# IronKid_ISTA.net
KiCad netlist of a schematic drawn in EAGLE
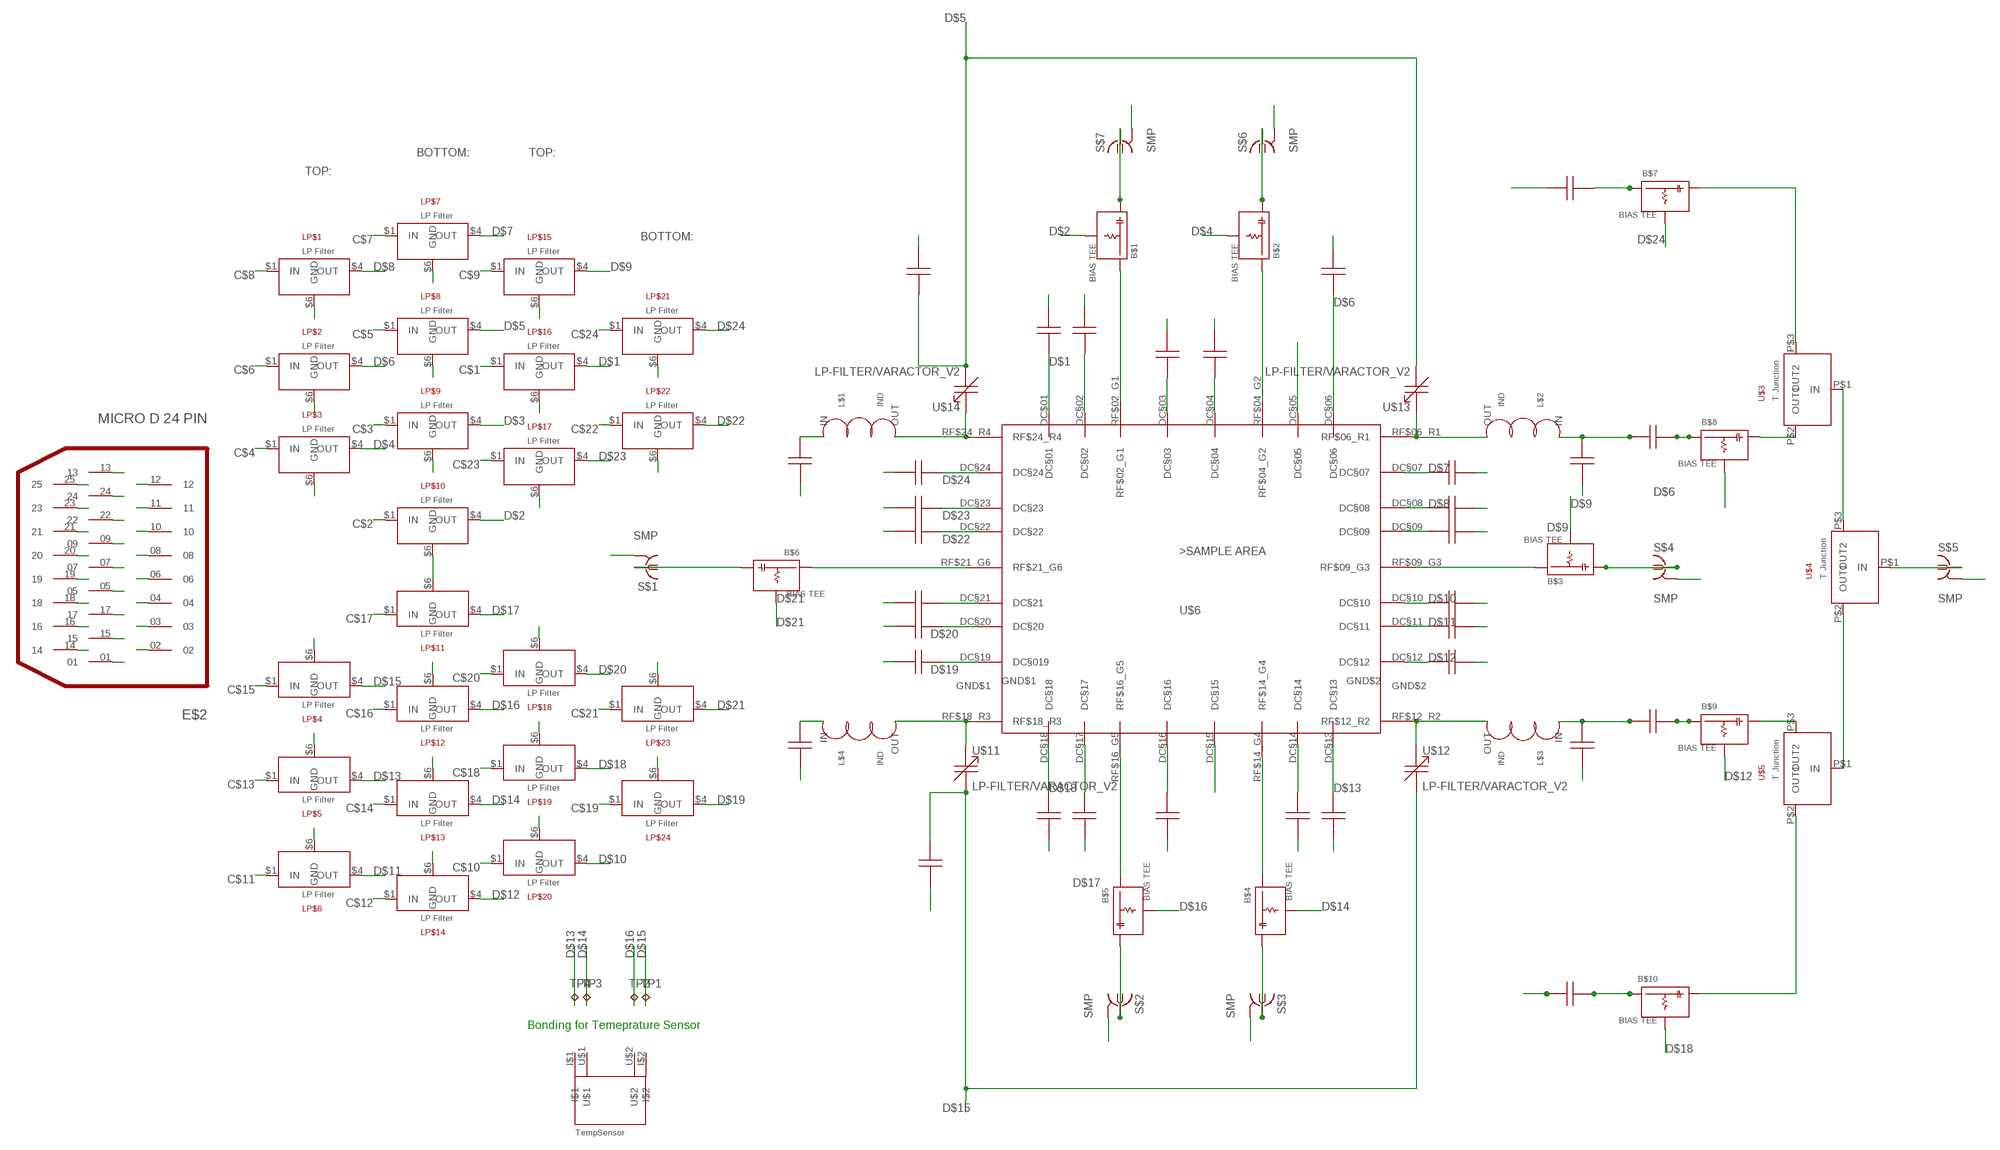
[diagram p0: schematic, sheet 1, part 1 of 2]
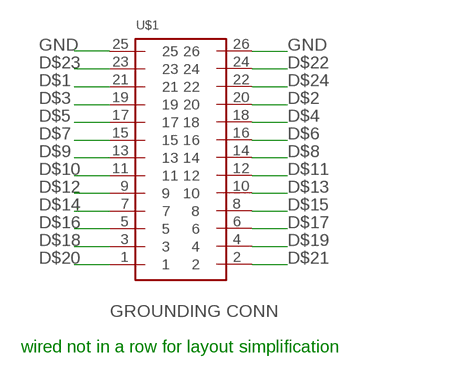
[diagram p1: schematic, sheet 1, part 2 of 2]

(export (version "E")
  (design (tool "Eeschema 10.0.6"))
  (components
    (comp (ref "B$1")
      (value "BIASTEEDOWN2")
      (footprint "eagle-import:BIAS_TEE_DOWN_0603_V02")
      (libsource (lib "eagle-import") (part "BIASTEEDOWN2"))
    )
    (comp (ref "B$2")
      (value "BIASTEEUP1")
      (footprint "eagle-import:BIAS_TEE_UP_0603")
      (libsource (lib "eagle-import") (part "BIASTEEUP1"))
    )
    (comp (ref "B$3")
      (value "BIASTEEDOWN1")
      (footprint "eagle-import:BIAS_TEE_DOWN_0603")
      (libsource (lib "eagle-import") (part "BIASTEEDOWN1"))
    )
    (comp (ref "B$4")
      (value "BIASTEEDOWN1")
      (footprint "eagle-import:BIAS_TEE_DOWN_0603")
      (libsource (lib "eagle-import") (part "BIASTEEDOWN1"))
    )
    (comp (ref "B$5")
      (value "BIASTEEUP2")
      (footprint "eagle-import:BIAS_TEE_UP_0603_V02")
      (libsource (lib "eagle-import") (part "BIASTEEUP2"))
    )
    (comp (ref "B$6")
      (value "BIASTEEDOWN1")
      (footprint "eagle-import:BIAS_TEE_DOWN_0603")
      (libsource (lib "eagle-import") (part "BIASTEEDOWN1"))
    )
    (comp (ref "B$7")
      (value "BIASTEEUP1")
      (footprint "eagle-import:BIAS_TEE_UP_0603")
      (libsource (lib "eagle-import") (part "BIASTEEUP1"))
    )
    (comp (ref "B$8")
      (value "BIASTEEDOWN1")
      (footprint "eagle-import:BIAS_TEE_DOWN_0603")
      (libsource (lib "eagle-import") (part "BIASTEEDOWN1"))
    )
    (comp (ref "B$9")
      (value "BIASTEEUP1")
      (footprint "eagle-import:BIAS_TEE_UP_0603")
      (libsource (lib "eagle-import") (part "BIASTEEUP1"))
    )
    (comp (ref "B$10")
      (value "BIASTEEDOWN1")
      (footprint "eagle-import:BIAS_TEE_DOWN_0603")
      (libsource (lib "eagle-import") (part "BIASTEEDOWN1"))
    )
    (comp (ref "E$2")
      (value "25_SOCKET_M83513(13-DPINOUT2")
      (footprint "eagle-import:25_SOCKET_M83513_13-D_V2")
      (libsource (lib "eagle-import") (part "25_SOCKET_M83513(13-DPINOUT2"))
    )
    (comp (ref "L$1")
      (value "L_MATCH")
      (footprint "eagle-import:L_MATCH")
      (libsource (lib "eagle-import") (part "L_MATCH"))
    )
    (comp (ref "L$2")
      (value "L_MATCH")
      (footprint "eagle-import:L_MATCH")
      (libsource (lib "eagle-import") (part "L_MATCH"))
    )
    (comp (ref "L$3")
      (value "L_MATCH")
      (footprint "eagle-import:L_MATCH")
      (libsource (lib "eagle-import") (part "L_MATCH"))
    )
    (comp (ref "L$4")
      (value "L_MATCH")
      (footprint "eagle-import:L_MATCH")
      (libsource (lib "eagle-import") (part "L_MATCH"))
    )
    (comp (ref "LP$1")
      (value "LP-FILTER/1-STAGETOP")
      (footprint "eagle-import:LP-FILTER_1_STAGE_OS_0603_TOP")
      (libsource (lib "eagle-import") (part "LP-FILTER/1-STAGETOP"))
    )
    (comp (ref "LP$2")
      (value "LP-FILTER/1-STAGETOP")
      (footprint "eagle-import:LP-FILTER_1_STAGE_OS_0603_TOP")
      (libsource (lib "eagle-import") (part "LP-FILTER/1-STAGETOP"))
    )
    (comp (ref "LP$3")
      (value "LP-FILTER/1-STAGETOP")
      (footprint "eagle-import:LP-FILTER_1_STAGE_OS_0603_TOP")
      (libsource (lib "eagle-import") (part "LP-FILTER/1-STAGETOP"))
    )
    (comp (ref "LP$4")
      (value "LP-FILTER/1-STAGETOP")
      (footprint "eagle-import:LP-FILTER_1_STAGE_OS_0603_TOP")
      (libsource (lib "eagle-import") (part "LP-FILTER/1-STAGETOP"))
    )
    (comp (ref "LP$5")
      (value "LP-FILTER/1-STAGETOP")
      (footprint "eagle-import:LP-FILTER_1_STAGE_OS_0603_TOP")
      (libsource (lib "eagle-import") (part "LP-FILTER/1-STAGETOP"))
    )
    (comp (ref "LP$6")
      (value "LP-FILTER/1-STAGETOP")
      (footprint "eagle-import:LP-FILTER_1_STAGE_OS_0603_TOP")
      (libsource (lib "eagle-import") (part "LP-FILTER/1-STAGETOP"))
    )
    (comp (ref "LP$7")
      (value "LP-FILTER/1-STAGEBOT")
      (footprint "eagle-import:LP-FILTER_1_STAGE_OS_0603_BOTTOM")
      (libsource (lib "eagle-import") (part "LP-FILTER/1-STAGEBOT"))
    )
    (comp (ref "LP$8")
      (value "LP-FILTER/1-STAGEBOT")
      (footprint "eagle-import:LP-FILTER_1_STAGE_OS_0603_BOTTOM")
      (libsource (lib "eagle-import") (part "LP-FILTER/1-STAGEBOT"))
    )
    (comp (ref "LP$9")
      (value "LP-FILTER/1-STAGEBOT")
      (footprint "eagle-import:LP-FILTER_1_STAGE_OS_0603_BOTTOM")
      (libsource (lib "eagle-import") (part "LP-FILTER/1-STAGEBOT"))
    )
    (comp (ref "LP$10")
      (value "LP-FILTER/1-STAGEBOT")
      (footprint "eagle-import:LP-FILTER_1_STAGE_OS_0603_BOTTOM")
      (libsource (lib "eagle-import") (part "LP-FILTER/1-STAGEBOT"))
    )
    (comp (ref "LP$11")
      (value "LP-FILTER/1-STAGEBOT")
      (footprint "eagle-import:LP-FILTER_1_STAGE_OS_0603_BOTTOM")
      (libsource (lib "eagle-import") (part "LP-FILTER/1-STAGEBOT"))
    )
    (comp (ref "LP$12")
      (value "LP-FILTER/1-STAGEBOT")
      (footprint "eagle-import:LP-FILTER_1_STAGE_OS_0603_BOTTOM")
      (libsource (lib "eagle-import") (part "LP-FILTER/1-STAGEBOT"))
    )
    (comp (ref "LP$13")
      (value "LP-FILTER/1-STAGEBOT")
      (footprint "eagle-import:LP-FILTER_1_STAGE_OS_0603_BOTTOM")
      (libsource (lib "eagle-import") (part "LP-FILTER/1-STAGEBOT"))
    )
    (comp (ref "LP$14")
      (value "LP-FILTER/1-STAGEBOT")
      (footprint "eagle-import:LP-FILTER_1_STAGE_OS_0603_BOTTOM")
      (libsource (lib "eagle-import") (part "LP-FILTER/1-STAGEBOT"))
    )
    (comp (ref "LP$15")
      (value "LP-FILTER/1-STAGETOP")
      (footprint "eagle-import:LP-FILTER_1_STAGE_OS_0603_TOP")
      (libsource (lib "eagle-import") (part "LP-FILTER/1-STAGETOP"))
    )
    (comp (ref "LP$16")
      (value "LP-FILTER/1-STAGETOP")
      (footprint "eagle-import:LP-FILTER_1_STAGE_OS_0603_TOP")
      (libsource (lib "eagle-import") (part "LP-FILTER/1-STAGETOP"))
    )
    (comp (ref "LP$17")
      (value "LP-FILTER/1-STAGETOP")
      (footprint "eagle-import:LP-FILTER_1_STAGE_OS_0603_TOP")
      (libsource (lib "eagle-import") (part "LP-FILTER/1-STAGETOP"))
    )
    (comp (ref "LP$18")
      (value "LP-FILTER/1-STAGETOP")
      (footprint "eagle-import:LP-FILTER_1_STAGE_OS_0603_TOP")
      (libsource (lib "eagle-import") (part "LP-FILTER/1-STAGETOP"))
    )
    (comp (ref "LP$19")
      (value "LP-FILTER/1-STAGETOP")
      (footprint "eagle-import:LP-FILTER_1_STAGE_OS_0603_TOP")
      (libsource (lib "eagle-import") (part "LP-FILTER/1-STAGETOP"))
    )
    (comp (ref "LP$20")
      (value "LP-FILTER/1-STAGETOP")
      (footprint "eagle-import:LP-FILTER_1_STAGE_OS_0603_TOP")
      (libsource (lib "eagle-import") (part "LP-FILTER/1-STAGETOP"))
    )
    (comp (ref "LP$21")
      (value "LP-FILTER/1-STAGEBOT")
      (footprint "eagle-import:LP-FILTER_1_STAGE_OS_0603_BOTTOM")
      (libsource (lib "eagle-import") (part "LP-FILTER/1-STAGEBOT"))
    )
    (comp (ref "LP$22")
      (value "LP-FILTER/1-STAGEBOT")
      (footprint "eagle-import:LP-FILTER_1_STAGE_OS_0603_BOTTOM")
      (libsource (lib "eagle-import") (part "LP-FILTER/1-STAGEBOT"))
    )
    (comp (ref "LP$23")
      (value "LP-FILTER/1-STAGEBOT")
      (footprint "eagle-import:LP-FILTER_1_STAGE_OS_0603_BOTTOM")
      (libsource (lib "eagle-import") (part "LP-FILTER/1-STAGEBOT"))
    )
    (comp (ref "LP$24")
      (value "LP-FILTER/1-STAGEBOT")
      (footprint "eagle-import:LP-FILTER_1_STAGE_OS_0603_BOTTOM")
      (libsource (lib "eagle-import") (part "LP-FILTER/1-STAGEBOT"))
    )
    (comp (ref "S$1")
      (value "MC-921WIDE")
      (footprint "eagle-import:SMP_STRAIGHT_MINI_WIDE")
      (libsource (lib "eagle-import") (part "MC-921WIDE"))
    )
    (comp (ref "S$2")
      (value "MC-921WIDE")
      (footprint "eagle-import:SMP_STRAIGHT_MINI_WIDE")
      (libsource (lib "eagle-import") (part "MC-921WIDE"))
    )
    (comp (ref "S$3")
      (value "MC-921WIDE")
      (footprint "eagle-import:SMP_STRAIGHT_MINI_WIDE")
      (libsource (lib "eagle-import") (part "MC-921WIDE"))
    )
    (comp (ref "S$4")
      (value "MC-921WIDE")
      (footprint "eagle-import:SMP_STRAIGHT_MINI_WIDE")
      (libsource (lib "eagle-import") (part "MC-921WIDE"))
    )
    (comp (ref "S$5")
      (value "MC-921WIDE")
      (footprint "eagle-import:SMP_STRAIGHT_MINI_WIDE")
      (libsource (lib "eagle-import") (part "MC-921WIDE"))
    )
    (comp (ref "S$6")
      (value "MC-921WIDE")
      (footprint "eagle-import:SMP_STRAIGHT_MINI_WIDE")
      (libsource (lib "eagle-import") (part "MC-921WIDE"))
    )
    (comp (ref "S$7")
      (value "MC-921WIDE")
      (footprint "eagle-import:SMP_STRAIGHT_MINI_WIDE")
      (libsource (lib "eagle-import") (part "MC-921WIDE"))
    )
    (comp (ref "TP1")
      (value "TPTP07SQ")
      (footprint "eagle-import:TP07SQ")
      (libsource (lib "eagle-import") (part "TPTP07SQ"))
    )
    (comp (ref "TP2")
      (value "TPTP07SQ")
      (footprint "eagle-import:TP07SQ")
      (libsource (lib "eagle-import") (part "TPTP07SQ"))
    )
    (comp (ref "TP3")
      (value "TPTP07SQ")
      (footprint "eagle-import:TP07SQ")
      (libsource (lib "eagle-import") (part "TPTP07SQ"))
    )
    (comp (ref "TP4")
      (value "TPTP07SQ")
      (footprint "eagle-import:TP07SQ")
      (libsource (lib "eagle-import") (part "TPTP07SQ"))
    )
    (comp (ref "U$1")
      (value "MEC8-113-02-L-D-RA1MBRD")
      (footprint "eagle-import:MEC8-113-02-L-D-RA1")
      (libsource (lib "eagle-import") (part "MEC8-113-02-L-D-RA1MBRD"))
    )
    (comp (ref "U$2")
      (value "TEMPSENS")
      (footprint "eagle-import:RX-BR_V1")
      (libsource (lib "eagle-import") (part "TEMPSENS"))
    )
    (comp (ref "U$3")
      (value "TJUNCTION")
      (footprint "eagle-import:T_JUNCTION_0.3MM")
      (libsource (lib "eagle-import") (part "TJUNCTION"))
    )
    (comp (ref "U$4")
      (value "TJUNCTION")
      (footprint "eagle-import:T_JUNCTION_0.3MM")
      (libsource (lib "eagle-import") (part "TJUNCTION"))
    )
    (comp (ref "U$5")
      (value "TJUNCTION")
      (footprint "eagle-import:T_JUNCTION_0.3MM")
      (libsource (lib "eagle-import") (part "TJUNCTION"))
    )
    (comp (ref "U$6")
      (value "24DC+10RF_V3.0")
      (footprint "eagle-import:24DC+10RF_400MU-PADS_0.7X0.7_V3.0")
      (libsource (lib "eagle-import") (part "24DC+10RF_V3.0"))
    )
    (comp (ref "U$7")
      (value "LP-FILTER/CAPACITOR/0603THIN")
      (footprint "eagle-import:LP-FILTER_CAPACITOR_0603_BOTTOM")
      (libsource (lib "eagle-import") (part "LP-FILTER/CAPACITOR/0603THIN"))
    )
    (comp (ref "U$8")
      (value "LP-FILTER/CAPACITOR/0603THIN")
      (footprint "eagle-import:LP-FILTER_CAPACITOR_0603_BOTTOM")
      (libsource (lib "eagle-import") (part "LP-FILTER/CAPACITOR/0603THIN"))
    )
    (comp (ref "U$9")
      (value "LP-FILTER/CAPACITOR/0603THIN")
      (footprint "eagle-import:LP-FILTER_CAPACITOR_0603_BOTTOM")
      (libsource (lib "eagle-import") (part "LP-FILTER/CAPACITOR/0603THIN"))
    )
    (comp (ref "U$10")
      (value "LP-FILTER/CAPACITOR/0603THIN")
      (footprint "eagle-import:LP-FILTER_CAPACITOR_0603_BOTTOM")
      (libsource (lib "eagle-import") (part "LP-FILTER/CAPACITOR/0603THIN"))
    )
    (comp (ref "U$11")
      (value "LP-FILTER/VARACTOR_V2")
      (footprint "eagle-import:LP-FILTER_VARACTOR_V2")
      (libsource (lib "eagle-import") (part "LP-FILTER/VARACTOR_V2"))
    )
    (comp (ref "U$12")
      (value "LP-FILTER/VARACTOR_V2")
      (footprint "eagle-import:LP-FILTER_VARACTOR_V2")
      (libsource (lib "eagle-import") (part "LP-FILTER/VARACTOR_V2"))
    )
    (comp (ref "U$13")
      (value "LP-FILTER/VARACTOR_V2")
      (footprint "eagle-import:LP-FILTER_VARACTOR_V2")
      (libsource (lib "eagle-import") (part "LP-FILTER/VARACTOR_V2"))
    )
    (comp (ref "U$14")
      (value "LP-FILTER/VARACTOR_V2")
      (footprint "eagle-import:LP-FILTER_VARACTOR_V2")
      (libsource (lib "eagle-import") (part "LP-FILTER/VARACTOR_V2"))
    )
    (comp (ref "U$15")
      (value "LP-FILTER/CAPACITOR/0603NORMAL")
      (footprint "eagle-import:LP-FILTER_CAPACITOR_0603_BOTTOM_V2")
      (libsource (lib "eagle-import") (part "LP-FILTER/CAPACITOR/0603NORMAL"))
    )
    (comp (ref "U$16")
      (value "LP-FILTER/CAPACITOR/0603NORMAL")
      (footprint "eagle-import:LP-FILTER_CAPACITOR_0603_BOTTOM_V2")
      (libsource (lib "eagle-import") (part "LP-FILTER/CAPACITOR/0603NORMAL"))
    )
    (comp (ref "U$17")
      (value "LP-FILTER/CAPACITOR/0603THIN")
      (footprint "eagle-import:LP-FILTER_CAPACITOR_0603_BOTTOM")
      (libsource (lib "eagle-import") (part "LP-FILTER/CAPACITOR/0603THIN"))
    )
    (comp (ref "U$18")
      (value "LP-FILTER/CAPACITOR/0603THIN")
      (footprint "eagle-import:LP-FILTER_CAPACITOR_0603_BOTTOM")
      (libsource (lib "eagle-import") (part "LP-FILTER/CAPACITOR/0603THIN"))
    )
    (comp (ref "U$19")
      (value "LP-FILTER/CAPACITOR/0603THIN")
      (footprint "eagle-import:LP-FILTER_CAPACITOR_0603_BOTTOM")
      (libsource (lib "eagle-import") (part "LP-FILTER/CAPACITOR/0603THIN"))
    )
    (comp (ref "U$20")
      (value "LP-FILTER/CAPACITOR/0603THIN")
      (footprint "eagle-import:LP-FILTER_CAPACITOR_0603_BOTTOM")
      (libsource (lib "eagle-import") (part "LP-FILTER/CAPACITOR/0603THIN"))
    )
    (comp (ref "U$21")
      (value "LP-FILTER/CAPACITOR/0603NORMAL")
      (footprint "eagle-import:LP-FILTER_CAPACITOR_0603_BOTTOM_V2")
      (libsource (lib "eagle-import") (part "LP-FILTER/CAPACITOR/0603NORMAL"))
    )
    (comp (ref "U$22")
      (value "LP-FILTER/CAPACITOR/0603NORMAL")
      (footprint "eagle-import:LP-FILTER_CAPACITOR_0603_BOTTOM_V2")
      (libsource (lib "eagle-import") (part "LP-FILTER/CAPACITOR/0603NORMAL"))
    )
    (comp (ref "U$23")
      (value "LP-FILTER/CAPACITOR/0603NORMAL")
      (footprint "eagle-import:LP-FILTER_CAPACITOR_0603_BOTTOM_V2")
      (libsource (lib "eagle-import") (part "LP-FILTER/CAPACITOR/0603NORMAL"))
    )
    (comp (ref "U$24")
      (value "LP-FILTER/CAPACITOR/0603NORMAL")
      (footprint "eagle-import:LP-FILTER_CAPACITOR_0603_BOTTOM_V2")
      (libsource (lib "eagle-import") (part "LP-FILTER/CAPACITOR/0603NORMAL"))
    )
    (comp (ref "U$26")
      (value "LP-FILTER/CAPACITOR/0603NORMAL")
      (footprint "eagle-import:LP-FILTER_CAPACITOR_0603_BOTTOM_V2")
      (libsource (lib "eagle-import") (part "LP-FILTER/CAPACITOR/0603NORMAL"))
    )
    (comp (ref "U$27")
      (value "LP-FILTER/CAPACITOR/0603NORMAL")
      (footprint "eagle-import:LP-FILTER_CAPACITOR_0603_BOTTOM_V2")
      (libsource (lib "eagle-import") (part "LP-FILTER/CAPACITOR/0603NORMAL"))
    )
    (comp (ref "U$28")
      (value "LP-FILTER/CAPACITOR/0603NORMAL")
      (footprint "eagle-import:LP-FILTER_CAPACITOR_0603_BOTTOM_V2")
      (libsource (lib "eagle-import") (part "LP-FILTER/CAPACITOR/0603NORMAL"))
    )
    (comp (ref "U$29")
      (value "LP-FILTER/CAPACITOR/0603NORMAL")
      (footprint "eagle-import:LP-FILTER_CAPACITOR_0603_BOTTOM_V2")
      (libsource (lib "eagle-import") (part "LP-FILTER/CAPACITOR/0603NORMAL"))
    )
    (comp (ref "U$30")
      (value "LP-FILTER/CAPACITOR/0603NORMAL")
      (footprint "eagle-import:LP-FILTER_CAPACITOR_0603_BOTTOM_V2")
      (libsource (lib "eagle-import") (part "LP-FILTER/CAPACITOR/0603NORMAL"))
    )
    (comp (ref "U$31")
      (value "LP-FILTER/CAPACITOR/0603NORMAL")
      (footprint "eagle-import:LP-FILTER_CAPACITOR_0603_BOTTOM_V2")
      (libsource (lib "eagle-import") (part "LP-FILTER/CAPACITOR/0603NORMAL"))
    )
    (comp (ref "U$32")
      (value "LP-FILTER/CAPACITOR/0603NORMAL")
      (footprint "eagle-import:LP-FILTER_CAPACITOR_0603_BOTTOM_V2")
      (libsource (lib "eagle-import") (part "LP-FILTER/CAPACITOR/0603NORMAL"))
    )
    (comp (ref "U$33")
      (value "LP-FILTER/CAPACITOR/0603NORMAL")
      (footprint "eagle-import:LP-FILTER_CAPACITOR_0603_BOTTOM_V2")
      (libsource (lib "eagle-import") (part "LP-FILTER/CAPACITOR/0603NORMAL"))
    )
    (comp (ref "U$34")
      (value "LP-FILTER/CAPACITOR/0603NORMAL")
      (footprint "eagle-import:LP-FILTER_CAPACITOR_0603_BOTTOM_V2")
      (libsource (lib "eagle-import") (part "LP-FILTER/CAPACITOR/0603NORMAL"))
    )
    (comp (ref "U$36")
      (value "LP-FILTER/CAPACITOR/0603NORMAL")
      (footprint "eagle-import:LP-FILTER_CAPACITOR_0603_BOTTOM_V2")
      (libsource (lib "eagle-import") (part "LP-FILTER/CAPACITOR/0603NORMAL"))
    )
    (comp (ref "U$37")
      (value "LP-FILTER/CAPACITOR/0603NORMAL")
      (footprint "eagle-import:LP-FILTER_CAPACITOR_0603_BOTTOM_V2")
      (libsource (lib "eagle-import") (part "LP-FILTER/CAPACITOR/0603NORMAL"))
    )
    (comp (ref "U$38")
      (value "LP-FILTER/CAPACITOR/0603NORMAL")
      (footprint "eagle-import:LP-FILTER_CAPACITOR_0603_BOTTOM_V2")
      (libsource (lib "eagle-import") (part "LP-FILTER/CAPACITOR/0603NORMAL"))
    )
    (comp (ref "U$39")
      (value "LP-FILTER/CAPACITOR/0603NORMAL")
      (footprint "eagle-import:LP-FILTER_CAPACITOR_0603_BOTTOM_V2")
      (libsource (lib "eagle-import") (part "LP-FILTER/CAPACITOR/0603NORMAL"))
    )
    (comp (ref "U$40")
      (value "LP-FILTER/CAPACITOR/0603NORMAL")
      (footprint "eagle-import:LP-FILTER_CAPACITOR_0603_BOTTOM_V2")
      (libsource (lib "eagle-import") (part "LP-FILTER/CAPACITOR/0603NORMAL"))
    )
    (comp (ref "U$41")
      (value "LP-FILTER/CAPACITOR/0603NORMAL")
      (footprint "eagle-import:LP-FILTER_CAPACITOR_0603_BOTTOM_V2")
      (libsource (lib "eagle-import") (part "LP-FILTER/CAPACITOR/0603NORMAL"))
    )
    (comp (ref "U$42")
      (value "LP-FILTER/CAPACITOR/0603NORMAL")
      (footprint "eagle-import:LP-FILTER_CAPACITOR_0603_BOTTOM_V2")
      (libsource (lib "eagle-import") (part "LP-FILTER/CAPACITOR/0603NORMAL"))
    )
    (comp (ref "U$43")
      (value "LP-FILTER/CAPACITOR/0603NORMAL")
      (footprint "eagle-import:LP-FILTER_CAPACITOR_0603_BOTTOM_V2")
      (libsource (lib "eagle-import") (part "LP-FILTER/CAPACITOR/0603NORMAL"))
    )
    (comp (ref "U$44")
      (value "LP-FILTER/CAPACITOR/0603NORMAL")
      (footprint "eagle-import:LP-FILTER_CAPACITOR_0603_BOTTOM_V2")
      (libsource (lib "eagle-import") (part "LP-FILTER/CAPACITOR/0603NORMAL"))
    )
  )
  (nets
    (net (code "1") (name "/C$1") (class "Default")
      (node (ref "E$2") (pin "01") (pinfunction "01_01") (pintype "bidirectional"))
      (node (ref "LP$16") (pin "$1") (pinfunction "IN_$1") (pintype "bidirectional"))
    )
    (net (code "2") (name "/C$2") (class "Default")
      (node (ref "E$2") (pin "02") (pinfunction "02_02") (pintype "bidirectional"))
      (node (ref "LP$10") (pin "$1") (pinfunction "IN_$1") (pintype "bidirectional"))
    )
    (net (code "3") (name "/C$3") (class "Default")
      (node (ref "E$2") (pin "03") (pinfunction "03_03") (pintype "bidirectional"))
      (node (ref "LP$9") (pin "$1") (pinfunction "IN_$1") (pintype "bidirectional"))
    )
    (net (code "4") (name "/C$4") (class "Default")
      (node (ref "E$2") (pin "04") (pinfunction "04_04") (pintype "bidirectional"))
      (node (ref "LP$3") (pin "$1") (pinfunction "IN_$1") (pintype "bidirectional"))
    )
    (net (code "5") (name "/C$5") (class "Default")
      (node (ref "E$2") (pin "05") (pinfunction "05_05") (pintype "bidirectional"))
      (node (ref "LP$8") (pin "$1") (pinfunction "IN_$1") (pintype "bidirectional"))
    )
    (net (code "6") (name "/C$6") (class "Default")
      (node (ref "E$2") (pin "06") (pinfunction "06_06") (pintype "bidirectional"))
      (node (ref "LP$2") (pin "$1") (pinfunction "IN_$1") (pintype "bidirectional"))
    )
    (net (code "7") (name "/C$7") (class "Default")
      (node (ref "E$2") (pin "07") (pinfunction "07_07") (pintype "bidirectional"))
      (node (ref "LP$7") (pin "$1") (pinfunction "IN_$1") (pintype "bidirectional"))
    )
    (net (code "8") (name "/C$8") (class "Default")
      (node (ref "E$2") (pin "08") (pinfunction "08_08") (pintype "bidirectional"))
      (node (ref "LP$1") (pin "$1") (pinfunction "IN_$1") (pintype "bidirectional"))
    )
    (net (code "9") (name "/C$9") (class "Default")
      (node (ref "E$2") (pin "09") (pinfunction "09_09") (pintype "bidirectional"))
      (node (ref "LP$15") (pin "$1") (pinfunction "IN_$1") (pintype "bidirectional"))
    )
    (net (code "10") (name "/C$10") (class "Default")
      (node (ref "E$2") (pin "10") (pinfunction "10_10") (pintype "bidirectional"))
      (node (ref "LP$20") (pin "$1") (pinfunction "IN_$1") (pintype "bidirectional"))
    )
    (net (code "11") (name "/C$11") (class "Default")
      (node (ref "E$2") (pin "11") (pinfunction "11_11") (pintype "bidirectional"))
      (node (ref "LP$6") (pin "$1") (pinfunction "IN_$1") (pintype "bidirectional"))
    )
    (net (code "12") (name "/C$12") (class "Default")
      (node (ref "E$2") (pin "12") (pinfunction "12_12") (pintype "bidirectional"))
      (node (ref "LP$14") (pin "$1") (pinfunction "IN_$1") (pintype "bidirectional"))
    )
    (net (code "13") (name "/C$13") (class "Default")
      (node (ref "E$2") (pin "13") (pinfunction "13_13") (pintype "bidirectional"))
      (node (ref "LP$5") (pin "$1") (pinfunction "IN_$1") (pintype "bidirectional"))
    )
    (net (code "14") (name "/C$14") (class "Default")
      (node (ref "E$2") (pin "14") (pinfunction "14_14") (pintype "bidirectional"))
      (node (ref "LP$13") (pin "$1") (pinfunction "IN_$1") (pintype "bidirectional"))
    )
    (net (code "15") (name "/C$15") (class "Default")
      (node (ref "E$2") (pin "15") (pinfunction "15_15") (pintype "bidirectional"))
      (node (ref "LP$4") (pin "$1") (pinfunction "IN_$1") (pintype "bidirectional"))
    )
    (net (code "16") (name "/C$16") (class "Default")
      (node (ref "E$2") (pin "16") (pinfunction "16_16") (pintype "bidirectional"))
      (node (ref "LP$12") (pin "$1") (pinfunction "IN_$1") (pintype "bidirectional"))
    )
    (net (code "17") (name "/C$17") (class "Default")
      (node (ref "E$2") (pin "17") (pinfunction "17_17") (pintype "bidirectional"))
      (node (ref "LP$11") (pin "$1") (pinfunction "IN_$1") (pintype "bidirectional"))
    )
    (net (code "18") (name "/C$18") (class "Default")
      (node (ref "E$2") (pin "18") (pinfunction "18_18") (pintype "bidirectional"))
      (node (ref "LP$19") (pin "$1") (pinfunction "IN_$1") (pintype "bidirectional"))
    )
    (net (code "19") (name "/C$19") (class "Default")
      (node (ref "E$2") (pin "19") (pinfunction "19_19") (pintype "bidirectional"))
      (node (ref "LP$24") (pin "$1") (pinfunction "IN_$1") (pintype "bidirectional"))
    )
    (net (code "20") (name "/C$20") (class "Default")
      (node (ref "E$2") (pin "20") (pinfunction "20_20") (pintype "bidirectional"))
      (node (ref "LP$18") (pin "$1") (pinfunction "IN_$1") (pintype "bidirectional"))
    )
    (net (code "21") (name "/C$21") (class "Default")
      (node (ref "E$2") (pin "21") (pinfunction "21_21") (pintype "bidirectional"))
      (node (ref "LP$23") (pin "$1") (pinfunction "IN_$1") (pintype "bidirectional"))
    )
    (net (code "22") (name "/C$22") (class "Default")
      (node (ref "E$2") (pin "22") (pinfunction "22_22") (pintype "bidirectional"))
      (node (ref "LP$22") (pin "$1") (pinfunction "IN_$1") (pintype "bidirectional"))
    )
    (net (code "23") (name "/C$23") (class "Default")
      (node (ref "E$2") (pin "23") (pinfunction "23_23") (pintype "bidirectional"))
      (node (ref "LP$17") (pin "$1") (pinfunction "IN_$1") (pintype "bidirectional"))
    )
    (net (code "24") (name "/C$24") (class "Default")
      (node (ref "E$2") (pin "24") (pinfunction "24_24") (pintype "bidirectional"))
      (node (ref "LP$21") (pin "$1") (pinfunction "IN_$1") (pintype "bidirectional"))
    )
    (net (code "25") (name "/D$1") (class "Default")
      (node (ref "LP$16") (pin "$4") (pinfunction "OUT_$4") (pintype "bidirectional"))
      (node (ref "U$1") (pin "21") (pinfunction "21_21") (pintype "bidirectional"))
      (node (ref "U$21") (pin "OUT") (pinfunction "2_OUT") (pintype "passive"))
      (node (ref "U$6") (pin "DC$01") (pinfunction "DC§01_DC$01") (pintype "bidirectional"))
    )
    (net (code "26") (name "/D$2") (class "Default")
      (node (ref "B$1") (pin "LF") (pinfunction "LF_LF") (pintype "bidirectional"))
      (node (ref "LP$10") (pin "$4") (pinfunction "OUT_$4") (pintype "bidirectional"))
      (node (ref "U$1") (pin "20") (pinfunction "20_20") (pintype "bidirectional"))
      (node (ref "U$22") (pin "OUT") (pinfunction "2_OUT") (pintype "passive"))
      (node (ref "U$6") (pin "DC§02") (pinfunction "DC§02_DC§02") (pintype "bidirectional"))
    )
    (net (code "27") (name "/D$3") (class "Default")
      (node (ref "LP$9") (pin "$4") (pinfunction "OUT_$4") (pintype "bidirectional"))
      (node (ref "U$1") (pin "19") (pinfunction "19_19") (pintype "bidirectional"))
      (node (ref "U$23") (pin "OUT") (pinfunction "2_OUT") (pintype "passive"))
      (node (ref "U$6") (pin "DC§03") (pinfunction "DC§03_DC§03") (pintype "bidirectional"))
    )
    (net (code "28") (name "/D$4") (class "Default")
      (node (ref "B$2") (pin "LF") (pinfunction "LF_LF") (pintype "bidirectional"))
      (node (ref "LP$3") (pin "$4") (pinfunction "OUT_$4") (pintype "bidirectional"))
      (node (ref "U$1") (pin "18") (pinfunction "18_18") (pintype "bidirectional"))
      (node (ref "U$24") (pin "OUT") (pinfunction "2_OUT") (pintype "passive"))
      (node (ref "U$6") (pin "DC§04") (pinfunction "DC§04_DC§04") (pintype "bidirectional"))
    )
    (net (code "29") (name "/D$5") (class "Default")
      (node (ref "LP$8") (pin "$4") (pinfunction "OUT_$4") (pintype "bidirectional"))
      (node (ref "U$1") (pin "17") (pinfunction "17_17") (pintype "bidirectional"))
      (node (ref "U$13") (pin "OUT1") (pinfunction "2_OUT1") (pintype "passive"))
      (node (ref "U$14") (pin "OUT1") (pinfunction "2_OUT1") (pintype "passive"))
      (node (ref "U$15") (pin "OUT") (pinfunction "2_OUT") (pintype "passive"))
      (node (ref "U$6") (pin "DC§05") (pinfunction "DC§05_DC§05") (pintype "bidirectional"))
    )
    (net (code "30") (name "/D$6") (class "Default")
      (node (ref "B$8") (pin "LF") (pinfunction "LF_LF") (pintype "bidirectional"))
      (node (ref "LP$2") (pin "$4") (pinfunction "OUT_$4") (pintype "bidirectional"))
      (node (ref "U$1") (pin "16") (pinfunction "16_16") (pintype "bidirectional"))
      (node (ref "U$26") (pin "OUT") (pinfunction "2_OUT") (pintype "passive"))
      (node (ref "U$6") (pin "DC§06") (pinfunction "DC§06_DC§06") (pintype "bidirectional"))
    )
    (net (code "31") (name "/D$7") (class "Default")
      (node (ref "LP$7") (pin "$4") (pinfunction "OUT_$4") (pintype "bidirectional"))
      (node (ref "U$1") (pin "15") (pinfunction "15_15") (pintype "bidirectional"))
      (node (ref "U$27") (pin "OUT") (pinfunction "2_OUT") (pintype "passive"))
      (node (ref "U$6") (pin "DC§07") (pinfunction "DC§07_DC§07") (pintype "bidirectional"))
    )
    (net (code "32") (name "/D$8") (class "Default")
      (node (ref "LP$1") (pin "$4") (pinfunction "OUT_$4") (pintype "bidirectional"))
      (node (ref "U$1") (pin "14") (pinfunction "14_14") (pintype "bidirectional"))
      (node (ref "U$28") (pin "OUT") (pinfunction "2_OUT") (pintype "passive"))
      (node (ref "U$6") (pin "DC§08") (pinfunction "DC§08_DC§08") (pintype "bidirectional"))
    )
    (net (code "33") (name "/D$9") (class "Default")
      (node (ref "B$3") (pin "LF") (pinfunction "LF_LF") (pintype "bidirectional"))
      (node (ref "LP$15") (pin "$4") (pinfunction "OUT_$4") (pintype "bidirectional"))
      (node (ref "U$1") (pin "13") (pinfunction "13_13") (pintype "bidirectional"))
      (node (ref "U$29") (pin "OUT") (pinfunction "2_OUT") (pintype "passive"))
      (node (ref "U$6") (pin "DC§09") (pinfunction "DC§09_DC§09") (pintype "bidirectional"))
    )
    (net (code "34") (name "/D$10") (class "Default")
      (node (ref "LP$20") (pin "$4") (pinfunction "OUT_$4") (pintype "bidirectional"))
      (node (ref "U$1") (pin "11") (pinfunction "11_11") (pintype "bidirectional"))
      (node (ref "U$30") (pin "OUT") (pinfunction "2_OUT") (pintype "passive"))
      (node (ref "U$6") (pin "DC§10") (pinfunction "DC§10_DC§10") (pintype "bidirectional"))
    )
    (net (code "35") (name "/D$11") (class "Default")
      (node (ref "LP$6") (pin "$4") (pinfunction "OUT_$4") (pintype "bidirectional"))
      (node (ref "U$1") (pin "12") (pinfunction "12_12") (pintype "bidirectional"))
      (node (ref "U$31") (pin "OUT") (pinfunction "2_OUT") (pintype "passive"))
      (node (ref "U$6") (pin "DC§11") (pinfunction "DC§11_DC§11") (pintype "bidirectional"))
    )
    (net (code "36") (name "/D$12") (class "Default")
      (node (ref "B$9") (pin "LF") (pinfunction "LF_LF") (pintype "bidirectional"))
      (node (ref "LP$14") (pin "$4") (pinfunction "OUT_$4") (pintype "bidirectional"))
      (node (ref "U$1") (pin "9") (pinfunction "9_9") (pintype "bidirectional"))
      (node (ref "U$32") (pin "OUT") (pinfunction "2_OUT") (pintype "passive"))
      (node (ref "U$6") (pin "DC§12") (pinfunction "DC§12_DC§12") (pintype "bidirectional"))
    )
    (net (code "37") (name "/D$13") (class "Default")
      (node (ref "LP$5") (pin "$4") (pinfunction "OUT_$4") (pintype "bidirectional"))
      (node (ref "TP4") (pin "TP") (pinfunction "TP_TP") (pintype "input"))
      (node (ref "U$1") (pin "10") (pinfunction "10_10") (pintype "bidirectional"))
      (node (ref "U$33") (pin "OUT") (pinfunction "2_OUT") (pintype "passive"))
      (node (ref "U$6") (pin "DC§13") (pinfunction "DC§13_DC§13") (pintype "bidirectional"))
    )
    (net (code "38") (name "/D$14") (class "Default")
      (node (ref "B$4") (pin "LF") (pinfunction "LF_LF") (pintype "bidirectional"))
      (node (ref "LP$13") (pin "$4") (pinfunction "OUT_$4") (pintype "bidirectional"))
      (node (ref "TP3") (pin "TP") (pinfunction "TP_TP") (pintype "input"))
      (node (ref "U$1") (pin "7") (pinfunction "7_7") (pintype "bidirectional"))
      (node (ref "U$34") (pin "OUT") (pinfunction "2_OUT") (pintype "passive"))
      (node (ref "U$6") (pin "DC§14") (pinfunction "DC§14_DC§14") (pintype "bidirectional"))
    )
    (net (code "39") (name "/D$15") (class "Default")
      (node (ref "LP$4") (pin "$4") (pinfunction "OUT_$4") (pintype "bidirectional"))
      (node (ref "TP1") (pin "TP") (pinfunction "TP_TP") (pintype "input"))
      (node (ref "U$1") (pin "8") (pinfunction "8_8") (pintype "bidirectional"))
      (node (ref "U$11") (pin "OUT1") (pinfunction "2_OUT1") (pintype "passive"))
      (node (ref "U$12") (pin "OUT1") (pinfunction "2_OUT1") (pintype "passive"))
      (node (ref "U$16") (pin "OUT") (pinfunction "2_OUT") (pintype "passive"))
      (node (ref "U$6") (pin "DC§15") (pinfunction "DC§15_DC§15") (pintype "bidirectional"))
    )
    (net (code "40") (name "/D$16") (class "Default")
      (node (ref "B$5") (pin "LF") (pinfunction "LF_LF") (pintype "bidirectional"))
      (node (ref "LP$12") (pin "$4") (pinfunction "OUT_$4") (pintype "bidirectional"))
      (node (ref "TP2") (pin "TP") (pinfunction "TP_TP") (pintype "input"))
      (node (ref "U$1") (pin "5") (pinfunction "5_5") (pintype "bidirectional"))
      (node (ref "U$36") (pin "OUT") (pinfunction "2_OUT") (pintype "passive"))
      (node (ref "U$6") (pin "DC§16") (pinfunction "DC§16_DC§16") (pintype "bidirectional"))
    )
    (net (code "41") (name "/D$17") (class "Default")
      (node (ref "LP$11") (pin "$4") (pinfunction "OUT_$4") (pintype "bidirectional"))
      (node (ref "U$1") (pin "6") (pinfunction "6_6") (pintype "bidirectional"))
      (node (ref "U$37") (pin "OUT") (pinfunction "2_OUT") (pintype "passive"))
      (node (ref "U$6") (pin "DC§17") (pinfunction "DC§17_DC§17") (pintype "bidirectional"))
    )
    (net (code "42") (name "/D$18") (class "Default")
      (node (ref "B$10") (pin "LF") (pinfunction "LF_LF") (pintype "bidirectional"))
      (node (ref "LP$19") (pin "$4") (pinfunction "OUT_$4") (pintype "bidirectional"))
      (node (ref "U$1") (pin "3") (pinfunction "3_3") (pintype "bidirectional"))
      (node (ref "U$38") (pin "OUT") (pinfunction "2_OUT") (pintype "passive"))
      (node (ref "U$6") (pin "DC§18") (pinfunction "DC§18_DC§18") (pintype "bidirectional"))
    )
    (net (code "43") (name "/D$19") (class "Default")
      (node (ref "LP$24") (pin "$4") (pinfunction "OUT_$4") (pintype "bidirectional"))
      (node (ref "U$1") (pin "4") (pinfunction "4_4") (pintype "bidirectional"))
      (node (ref "U$39") (pin "OUT") (pinfunction "2_OUT") (pintype "passive"))
      (node (ref "U$6") (pin "DC§19") (pinfunction "DC§019_DC§19") (pintype "bidirectional"))
    )
    (net (code "44") (name "/D$20") (class "Default")
      (node (ref "LP$18") (pin "$4") (pinfunction "OUT_$4") (pintype "bidirectional"))
      (node (ref "U$1") (pin "1") (pinfunction "1_1") (pintype "bidirectional"))
      (node (ref "U$40") (pin "OUT") (pinfunction "2_OUT") (pintype "passive"))
      (node (ref "U$6") (pin "DC§20") (pinfunction "DC§20_DC§20") (pintype "bidirectional"))
    )
    (net (code "45") (name "/D$21") (class "Default")
      (node (ref "B$6") (pin "LF") (pinfunction "LF_LF") (pintype "bidirectional"))
      (node (ref "LP$23") (pin "$4") (pinfunction "OUT_$4") (pintype "bidirectional"))
      (node (ref "U$1") (pin "2") (pinfunction "2_2") (pintype "bidirectional"))
      (node (ref "U$41") (pin "OUT") (pinfunction "2_OUT") (pintype "passive"))
      (node (ref "U$6") (pin "DC§21") (pinfunction "DC§21_DC§21") (pintype "bidirectional"))
    )
    (net (code "46") (name "/D$22") (class "Default")
      (node (ref "LP$22") (pin "$4") (pinfunction "OUT_$4") (pintype "bidirectional"))
      (node (ref "U$1") (pin "24") (pinfunction "24_24") (pintype "bidirectional"))
      (node (ref "U$42") (pin "OUT") (pinfunction "2_OUT") (pintype "passive"))
      (node (ref "U$6") (pin "DC§22") (pinfunction "DC§22_DC§22") (pintype "bidirectional"))
    )
    (net (code "47") (name "/D$23") (class "Default")
      (node (ref "LP$17") (pin "$4") (pinfunction "OUT_$4") (pintype "bidirectional"))
      (node (ref "U$1") (pin "23") (pinfunction "23_23") (pintype "bidirectional"))
      (node (ref "U$43") (pin "OUT") (pinfunction "2_OUT") (pintype "passive"))
      (node (ref "U$6") (pin "DC§23") (pinfunction "DC§23_DC§23") (pintype "bidirectional"))
    )
    (net (code "48") (name "/D$24") (class "Default")
      (node (ref "B$7") (pin "LF") (pinfunction "LF_LF") (pintype "bidirectional"))
      (node (ref "LP$21") (pin "$4") (pinfunction "OUT_$4") (pintype "bidirectional"))
      (node (ref "U$1") (pin "22") (pinfunction "22_22") (pintype "bidirectional"))
      (node (ref "U$44") (pin "OUT") (pinfunction "2_OUT") (pintype "passive"))
      (node (ref "U$6") (pin "DC§24") (pinfunction "DC§24_DC§24") (pintype "bidirectional"))
    )
    (net (code "49") (name "/GND") (class "Default")
      (node (ref "E$2") (pin "25") (pinfunction "25_25") (pintype "bidirectional"))
      (node (ref "LP$1") (pin "$6") (pinfunction "GND_$6") (pintype "bidirectional"))
      (node (ref "LP$10") (pin "$6") (pinfunction "GND_$6") (pintype "bidirectional"))
      (node (ref "LP$11") (pin "$6") (pinfunction "GND_$6") (pintype "bidirectional"))
      (node (ref "LP$12") (pin "$6") (pinfunction "GND_$6") (pintype "bidirectional"))
      (node (ref "LP$13") (pin "$6") (pinfunction "GND_$6") (pintype "bidirectional"))
      (node (ref "LP$14") (pin "$6") (pinfunction "GND_$6") (pintype "bidirectional"))
      (node (ref "LP$15") (pin "$6") (pinfunction "GND_$6") (pintype "bidirectional"))
      (node (ref "LP$16") (pin "$6") (pinfunction "GND_$6") (pintype "bidirectional"))
      (node (ref "LP$17") (pin "$6") (pinfunction "GND_$6") (pintype "bidirectional"))
      (node (ref "LP$18") (pin "$6") (pinfunction "GND_$6") (pintype "bidirectional"))
      (node (ref "LP$19") (pin "$6") (pinfunction "GND_$6") (pintype "bidirectional"))
      (node (ref "LP$2") (pin "$6") (pinfunction "GND_$6") (pintype "bidirectional"))
      (node (ref "LP$20") (pin "$6") (pinfunction "GND_$6") (pintype "bidirectional"))
      (node (ref "LP$21") (pin "$6") (pinfunction "GND_$6") (pintype "bidirectional"))
      (node (ref "LP$22") (pin "$6") (pinfunction "GND_$6") (pintype "bidirectional"))
      (node (ref "LP$23") (pin "$6") (pinfunction "GND_$6") (pintype "bidirectional"))
      (node (ref "LP$24") (pin "$6") (pinfunction "GND_$6") (pintype "bidirectional"))
      (node (ref "LP$3") (pin "$6") (pinfunction "GND_$6") (pintype "bidirectional"))
      (node (ref "LP$4") (pin "$6") (pinfunction "GND_$6") (pintype "bidirectional"))
      (node (ref "LP$5") (pin "$6") (pinfunction "GND_$6") (pintype "bidirectional"))
      (node (ref "LP$6") (pin "$6") (pinfunction "GND_$6") (pintype "bidirectional"))
      (node (ref "LP$7") (pin "$6") (pinfunction "GND_$6") (pintype "bidirectional"))
      (node (ref "LP$8") (pin "$6") (pinfunction "GND_$6") (pintype "bidirectional"))
      (node (ref "LP$9") (pin "$6") (pinfunction "GND_$6") (pintype "bidirectional"))
      (node (ref "S$1") (pin "2@1") (pinfunction "GND_2@1") (pintype "passive"))
      (node (ref "S$1") (pin "2@2") (pinfunction "GND_2@2") (pintype "passive"))
      (node (ref "S$2") (pin "2@1") (pinfunction "GND_2@1") (pintype "passive"))
      (node (ref "S$2") (pin "2@2") (pinfunction "GND_2@2") (pintype "passive"))
      (node (ref "S$3") (pin "2@1") (pinfunction "GND_2@1") (pintype "passive"))
      (node (ref "S$3") (pin "2@2") (pinfunction "GND_2@2") (pintype "passive"))
      (node (ref "S$4") (pin "2@1") (pinfunction "GND_2@1") (pintype "passive"))
      (node (ref "S$4") (pin "2@2") (pinfunction "GND_2@2") (pintype "passive"))
      (node (ref "S$5") (pin "2@1") (pinfunction "GND_2@1") (pintype "passive"))
      (node (ref "S$5") (pin "2@2") (pinfunction "GND_2@2") (pintype "passive"))
      (node (ref "S$6") (pin "2@1") (pinfunction "GND_2@1") (pintype "passive"))
      (node (ref "S$6") (pin "2@2") (pinfunction "GND_2@2") (pintype "passive"))
      (node (ref "S$7") (pin "2@1") (pinfunction "GND_2@1") (pintype "passive"))
      (node (ref "S$7") (pin "2@2") (pinfunction "GND_2@2") (pintype "passive"))
      (node (ref "U$1") (pin "25") (pinfunction "25_25") (pintype "bidirectional"))
      (node (ref "U$1") (pin "26") (pinfunction "26_26") (pintype "bidirectional"))
      (node (ref "U$10") (pin "OUT") (pinfunction "2_OUT") (pintype "passive"))
      (node (ref "U$15") (pin "IN") (pinfunction "1_IN") (pintype "passive"))
      (node (ref "U$16") (pin "IN") (pinfunction "1_IN") (pintype "passive"))
      (node (ref "U$21") (pin "IN") (pinfunction "1_IN") (pintype "passive"))
      (node (ref "U$22") (pin "IN") (pinfunction "1_IN") (pintype "passive"))
      (node (ref "U$23") (pin "IN") (pinfunction "1_IN") (pintype "passive"))
      (node (ref "U$24") (pin "IN") (pinfunction "1_IN") (pintype "passive"))
      (node (ref "U$26") (pin "IN") (pinfunction "1_IN") (pintype "passive"))
      (node (ref "U$27") (pin "IN") (pinfunction "1_IN") (pintype "passive"))
      (node (ref "U$28") (pin "IN") (pinfunction "1_IN") (pintype "passive"))
      (node (ref "U$29") (pin "IN") (pinfunction "1_IN") (pintype "passive"))
      (node (ref "U$30") (pin "IN") (pinfunction "1_IN") (pintype "passive"))
      (node (ref "U$31") (pin "IN") (pinfunction "1_IN") (pintype "passive"))
      (node (ref "U$32") (pin "IN") (pinfunction "1_IN") (pintype "passive"))
      (node (ref "U$33") (pin "IN") (pinfunction "1_IN") (pintype "passive"))
      (node (ref "U$34") (pin "IN") (pinfunction "1_IN") (pintype "passive"))
      (node (ref "U$36") (pin "IN") (pinfunction "1_IN") (pintype "passive"))
      (node (ref "U$37") (pin "IN") (pinfunction "1_IN") (pintype "passive"))
      (node (ref "U$38") (pin "IN") (pinfunction "1_IN") (pintype "passive"))
      (node (ref "U$39") (pin "IN") (pinfunction "1_IN") (pintype "passive"))
      (node (ref "U$40") (pin "IN") (pinfunction "1_IN") (pintype "passive"))
      (node (ref "U$41") (pin "IN") (pinfunction "1_IN") (pintype "passive"))
      (node (ref "U$42") (pin "IN") (pinfunction "1_IN") (pintype "passive"))
      (node (ref "U$43") (pin "IN") (pinfunction "1_IN") (pintype "passive"))
      (node (ref "U$44") (pin "IN") (pinfunction "1_IN") (pintype "passive"))
      (node (ref "U$7") (pin "OUT") (pinfunction "2_OUT") (pintype "passive"))
      (node (ref "U$8") (pin "OUT") (pinfunction "2_OUT") (pintype "passive"))
      (node (ref "U$9") (pin "OUT") (pinfunction "2_OUT") (pintype "passive"))
    )
    (net (code "50") (name "/RF$3") (class "Default")
      (node (ref "L$4") (pin "IN") (pinfunction "IN_IN") (pintype "passive"))
      (node (ref "U$18") (pin "IN") (pinfunction "1_IN") (pintype "passive"))
      (node (ref "U$8") (pin "IN") (pinfunction "1_IN") (pintype "passive"))
    )
    (net (code "51") (name "/RF$4") (class "Default")
      (node (ref "L$1") (pin "IN") (pinfunction "IN_IN") (pintype "passive"))
      (node (ref "U$17") (pin "IN") (pinfunction "1_IN") (pintype "passive"))
      (node (ref "U$7") (pin "IN") (pinfunction "1_IN") (pintype "passive"))
    )
    (net (code "52") (name "Net-(B$1-PadHF)") (class "Default")
      (node (ref "B$1") (pin "HF") (pinfunction "HF_HF") (pintype "bidirectional"))
      (node (ref "S$7") (pin "1") (pinfunction "1_1") (pintype "passive"))
    )
    (net (code "53") (name "Net-(B$1-PadOUT)") (class "Default")
      (node (ref "B$1") (pin "OUT") (pinfunction "OUT_OUT") (pintype "bidirectional"))
      (node (ref "U$6") (pin "RF$02_G1") (pinfunction "RF$02_G1_RF$02_G1") (pintype "bidirectional"))
    )
    (net (code "54") (name "Net-(B$2-PadHF)") (class "Default")
      (node (ref "B$2") (pin "HF") (pinfunction "HF_HF") (pintype "bidirectional"))
      (node (ref "S$6") (pin "1") (pinfunction "1_1") (pintype "passive"))
    )
    (net (code "55") (name "Net-(B$2-PadOUT)") (class "Default")
      (node (ref "B$2") (pin "OUT") (pinfunction "OUT_OUT") (pintype "bidirectional"))
      (node (ref "U$6") (pin "RF$04_G2") (pinfunction "RF$04_G2_RF$04_G2") (pintype "bidirectional"))
    )
    (net (code "56") (name "Net-(B$3-PadHF)") (class "Default")
      (node (ref "B$3") (pin "HF") (pinfunction "HF_HF") (pintype "bidirectional"))
      (node (ref "S$4") (pin "1") (pinfunction "1_1") (pintype "passive"))
    )
    (net (code "57") (name "Net-(B$3-PadOUT)") (class "Default")
      (node (ref "B$3") (pin "OUT") (pinfunction "OUT_OUT") (pintype "bidirectional"))
      (node (ref "U$6") (pin "RF$09_G3") (pinfunction "RF$09_G3_RF$09_G3") (pintype "bidirectional"))
    )
    (net (code "58") (name "Net-(B$4-PadHF)") (class "Default")
      (node (ref "B$4") (pin "HF") (pinfunction "HF_HF") (pintype "bidirectional"))
      (node (ref "S$3") (pin "1") (pinfunction "1_1") (pintype "passive"))
    )
    (net (code "59") (name "Net-(B$4-PadOUT)") (class "Default")
      (node (ref "B$4") (pin "OUT") (pinfunction "OUT_OUT") (pintype "bidirectional"))
      (node (ref "U$6") (pin "RF$14_G4") (pinfunction "RF$14_G4_RF$14_G4") (pintype "bidirectional"))
    )
    (net (code "60") (name "Net-(B$5-PadHF)") (class "Default")
      (node (ref "B$5") (pin "HF") (pinfunction "HF_HF") (pintype "bidirectional"))
      (node (ref "S$2") (pin "1") (pinfunction "1_1") (pintype "passive"))
    )
    (net (code "61") (name "Net-(B$5-PadOUT)") (class "Default")
      (node (ref "B$5") (pin "OUT") (pinfunction "OUT_OUT") (pintype "bidirectional"))
      (node (ref "U$6") (pin "RF$16_G5") (pinfunction "RF$16_G5_RF$16_G5") (pintype "bidirectional"))
    )
    (net (code "62") (name "Net-(B$6-PadHF)") (class "Default")
      (node (ref "B$6") (pin "HF") (pinfunction "HF_HF") (pintype "bidirectional"))
      (node (ref "S$1") (pin "1") (pinfunction "1_1") (pintype "passive"))
    )
    (net (code "63") (name "Net-(B$6-PadOUT)") (class "Default")
      (node (ref "B$6") (pin "OUT") (pinfunction "OUT_OUT") (pintype "bidirectional"))
      (node (ref "U$6") (pin "RF$21_G6") (pinfunction "RF$21_G6_RF$21_G6") (pintype "bidirectional"))
    )
    (net (code "64") (name "Net-(U$3-IN)") (class "Default")
      (node (ref "U$3") (pin "P$1") (pinfunction "IN_P$1") (pintype "bidirectional"))
      (node (ref "U$4") (pin "P$3") (pinfunction "OUT2_P$3") (pintype "bidirectional"))
    )
    (net (code "65") (name "Net-(U$3-OUT1)") (class "Default")
      (node (ref "B$8") (pin "HF") (pinfunction "HF_HF") (pintype "bidirectional"))
      (node (ref "U$3") (pin "P$2") (pinfunction "OUT1_P$2") (pintype "bidirectional"))
    )
    (net (code "66") (name "Net-(U$3-OUT2)") (class "Default")
      (node (ref "B$7") (pin "HF") (pinfunction "HF_HF") (pintype "bidirectional"))
      (node (ref "U$3") (pin "P$3") (pinfunction "OUT2_P$3") (pintype "bidirectional"))
    )
    (net (code "67") (name "Net-(U$4-IN)") (class "Default")
      (node (ref "S$5") (pin "1") (pinfunction "1_1") (pintype "passive"))
      (node (ref "U$4") (pin "P$1") (pinfunction "IN_P$1") (pintype "bidirectional"))
    )
    (net (code "68") (name "Net-(U$4-OUT1)") (class "Default")
      (node (ref "U$4") (pin "P$2") (pinfunction "OUT1_P$2") (pintype "bidirectional"))
      (node (ref "U$5") (pin "P$1") (pinfunction "IN_P$1") (pintype "bidirectional"))
    )
    (net (code "69") (name "Net-(U$5-OUT1)") (class "Default")
      (node (ref "B$10") (pin "HF") (pinfunction "HF_HF") (pintype "bidirectional"))
      (node (ref "U$5") (pin "P$2") (pinfunction "OUT1_P$2") (pintype "bidirectional"))
    )
    (net (code "70") (name "Net-(U$5-OUT2)") (class "Default")
      (node (ref "B$9") (pin "HF") (pinfunction "HF_HF") (pintype "bidirectional"))
      (node (ref "U$5") (pin "P$3") (pinfunction "OUT2_P$3") (pintype "bidirectional"))
    )
    (net (code "71") (name "Net-(U$10-1)") (class "Default")
      (node (ref "L$2") (pin "IN") (pinfunction "IN_IN") (pintype "passive"))
      (node (ref "U$10") (pin "IN") (pinfunction "1_IN") (pintype "passive"))
      (node (ref "U$19") (pin "IN") (pinfunction "1_IN") (pintype "passive"))
    )
    (net (code "72") (name "Net-(U$11-1)") (class "Default")
      (node (ref "L$4") (pin "OUT") (pinfunction "OUT_OUT") (pintype "passive"))
      (node (ref "U$11") (pin "OUT") (pinfunction "1_OUT") (pintype "passive"))
      (node (ref "U$6") (pin "RF$18_R3") (pinfunction "RF$18_R3_RF$18_R3") (pintype "bidirectional"))
    )
    (net (code "73") (name "Net-(U$12-1)") (class "Default")
      (node (ref "L$3") (pin "OUT") (pinfunction "OUT_OUT") (pintype "passive"))
      (node (ref "U$12") (pin "OUT") (pinfunction "1_OUT") (pintype "passive"))
      (node (ref "U$6") (pin "RF$12_R2") (pinfunction "RF$12_R2_RF$12_R2") (pintype "bidirectional"))
    )
    (net (code "74") (name "Net-(U$13-1)") (class "Default")
      (node (ref "L$2") (pin "OUT") (pinfunction "OUT_OUT") (pintype "passive"))
      (node (ref "U$13") (pin "OUT") (pinfunction "1_OUT") (pintype "passive"))
      (node (ref "U$6") (pin "RF$06_R1") (pinfunction "RF$06_R1_RF$06_R1") (pintype "bidirectional"))
    )
    (net (code "75") (name "Net-(U$14-1)") (class "Default")
      (node (ref "L$1") (pin "OUT") (pinfunction "OUT_OUT") (pintype "passive"))
      (node (ref "U$14") (pin "OUT") (pinfunction "1_OUT") (pintype "passive"))
      (node (ref "U$6") (pin "RF$24_R4") (pinfunction "RF$24_R4_RF$24_R4") (pintype "bidirectional"))
    )
    (net (code "76") (name "Net-(U$17-2)") (class "Default")
      (node (ref "B$7") (pin "OUT") (pinfunction "OUT_OUT") (pintype "bidirectional"))
      (node (ref "U$17") (pin "OUT") (pinfunction "2_OUT") (pintype "passive"))
    )
    (net (code "77") (name "Net-(U$18-2)") (class "Default")
      (node (ref "B$10") (pin "OUT") (pinfunction "OUT_OUT") (pintype "bidirectional"))
      (node (ref "U$18") (pin "OUT") (pinfunction "2_OUT") (pintype "passive"))
    )
    (net (code "78") (name "Net-(U$19-2)") (class "Default")
      (node (ref "B$8") (pin "OUT") (pinfunction "OUT_OUT") (pintype "bidirectional"))
      (node (ref "U$19") (pin "OUT") (pinfunction "2_OUT") (pintype "passive"))
    )
    (net (code "79") (name "Net-(U$20-1)") (class "Default")
      (node (ref "L$3") (pin "IN") (pinfunction "IN_IN") (pintype "passive"))
      (node (ref "U$20") (pin "IN") (pinfunction "1_IN") (pintype "passive"))
      (node (ref "U$9") (pin "IN") (pinfunction "1_IN") (pintype "passive"))
    )
    (net (code "80") (name "Net-(U$20-2)") (class "Default")
      (node (ref "B$9") (pin "OUT") (pinfunction "OUT_OUT") (pintype "bidirectional"))
      (node (ref "U$20") (pin "OUT") (pinfunction "2_OUT") (pintype "passive"))
    )
    (net (code "81") (name "unconnected-(U$2-PadI$1)") (class "Default")
      (node (ref "U$2") (pin "I$1") (pinfunction "I$1_I$1") (pintype "bidirectional"))
    )
    (net (code "82") (name "unconnected-(U$2-PadI$2)") (class "Default")
      (node (ref "U$2") (pin "I$2") (pinfunction "I$2_I$2") (pintype "bidirectional"))
    )
    (net (code "83") (name "unconnected-(U$2-PadU$1)") (class "Default")
      (node (ref "U$2") (pin "U$1") (pinfunction "U$1_U$1") (pintype "bidirectional"))
    )
    (net (code "84") (name "unconnected-(U$2-PadU$2)") (class "Default")
      (node (ref "U$2") (pin "U$2") (pinfunction "U$2_U$2") (pintype "bidirectional"))
    )
    (net (code "85") (name "unconnected-(U$6-PadGND$1)") (class "Default")
      (node (ref "U$6") (pin "GND$1") (pinfunction "GND$1_GND$1") (pintype "bidirectional"))
    )
    (net (code "86") (name "unconnected-(U$6-PadGND$2)") (class "Default")
      (node (ref "U$6") (pin "GND$2") (pinfunction "GND$2_GND$2") (pintype "bidirectional"))
    )
  )
)
